# dental-unit-AS5600_v1_0.net
KiCad netlist of a schematic drawn in Altium Designer
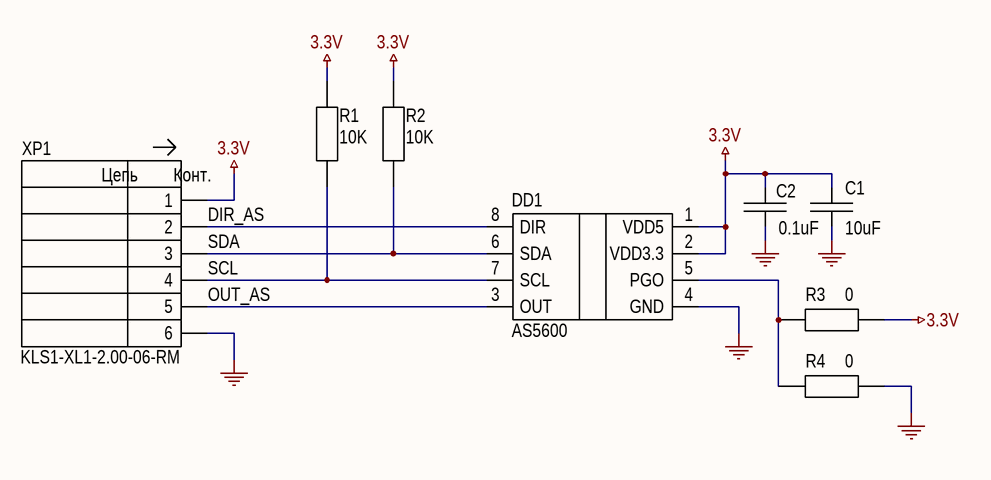
[diagram p0: dental-unit-AS5600 v1_0.SchDoc]

(export (version "E")
  (design (tool "Eeschema 10.0.6"))
  (components
    (comp (ref "C1")
      (value "10uF")
      (footprint "CC_0603")
      (description "Cap Ceramic, 0603, 10u, 10%, 16V, X5R (Sumsung)")
      (fields (field (name "Comment") "CL10A106KP8NNNC"))
      (libsource (lib "my_discrete_new") (part "C"))
    )
    (comp (ref "C2")
      (value "0.1uF")
      (footprint "CC_0603")
      (description "Cap Ceramic, 0603, 0.1u, 10%, 16V, X7R (Yageo)")
      (fields (field (name "Comment") "CC0603KRX7R5BB104"))
      (libsource (lib "my_discrete_new") (part "C"))
    )
    (comp (ref "DD1")
      (value "AS5600")
      (footprint "SOIC-8")
      (description "12-Bit Programmable Contactless\r\nPotentiometer")
      (libsource (lib "my_microschems_new") (part "AS5600"))
    )
    (comp (ref "R1")
      (value "10K")
      (footprint "RC_0603")
      (description "Res, 0603, 10K, 1%, 0.25W (ф. Yageo)")
      (fields (field (name "POWER") "0.25W") (field (name "Comment") "AC0603FR-0710KL"))
      (libsource (lib "my_discrete_new") (part "R"))
    )
    (comp (ref "R2")
      (value "10K")
      (footprint "RC_0603")
      (description "Res, 0603, 10K, 1%, 0.25W (ф. Yageo)")
      (fields (field (name "POWER") "0.25W") (field (name "Comment") "AC0603FR-0710KL"))
      (libsource (lib "my_discrete_new") (part "R"))
    )
    (comp (ref "R3")
      (value "0")
      (footprint "RC_0603")
      (description "Res, 0603, 0, 1%, 0.25W (ф. Yageo)")
      (fields (field (name "POWER") "0.25W") (field (name "Comment") "AC0603FR-070RL"))
      (libsource (lib "my_discrete_new") (part "R"))
    )
    (comp (ref "R4")
      (value "0")
      (footprint "RC_0603")
      (description "Res, 0603, 0, 1%, 0.25W (ф. Yageo)")
      (fields (field (name "POWER") "0.25W") (field (name "Comment") "AC0603FR-070RL"))
      (libsource (lib "my_discrete_new") (part "R"))
    )
    (comp (ref "XP1")
      (value "KLS1-XL1-2.00-06-RM")
      (footprint "KLS1-XL1-2.00-06-RM")
      (description "2.0mm, 6pin, KLS")
      (libsource (lib "my_connectors_new") (part "KLS1-XL1-2.00-06-x"))
    )
  )
  (nets
    (net (code "1") (name "/DIR_AS") (class "Default")
      (node (ref "DD1") (pin "8") (pinfunction "DIR_8") (pintype "passive"))
      (node (ref "XP1") (pin "2") (pinfunction "2_2") (pintype "passive"))
    )
    (net (code "2") (name "/OUT_AS") (class "Default")
      (node (ref "DD1") (pin "3") (pinfunction "OUT_3") (pintype "passive"))
      (node (ref "XP1") (pin "5") (pinfunction "5_5") (pintype "passive"))
    )
    (net (code "3") (name "/SCL") (class "Default")
      (node (ref "DD1") (pin "7") (pinfunction "SCL_7") (pintype "passive"))
      (node (ref "R1") (pin "1") (pinfunction "1_1") (pintype "passive"))
      (node (ref "XP1") (pin "4") (pinfunction "4_4") (pintype "passive"))
    )
    (net (code "4") (name "/SDA") (class "Default")
      (node (ref "DD1") (pin "6") (pinfunction "SDA_6") (pintype "passive"))
      (node (ref "R2") (pin "1") (pinfunction "1_1") (pintype "passive"))
      (node (ref "XP1") (pin "3") (pinfunction "3_3") (pintype "passive"))
    )
    (net (code "5") (name "3.3V") (class "Default")
      (node (ref "C1") (pin "2") (pinfunction "2_2") (pintype "passive"))
      (node (ref "C2") (pin "2") (pinfunction "2_2") (pintype "passive"))
      (node (ref "DD1") (pin "1") (pinfunction "VDD5_1") (pintype "passive"))
      (node (ref "DD1") (pin "2") (pinfunction "VDD3.3_2") (pintype "passive"))
      (node (ref "R1") (pin "2") (pinfunction "2_2") (pintype "passive"))
      (node (ref "R2") (pin "2") (pinfunction "2_2") (pintype "passive"))
      (node (ref "R3") (pin "2") (pinfunction "2_2") (pintype "passive"))
      (node (ref "XP1") (pin "1") (pinfunction "1_1") (pintype "passive"))
    )
    (net (code "6") (name "GND") (class "Default")
      (node (ref "C1") (pin "1") (pinfunction "1_1") (pintype "passive"))
      (node (ref "C2") (pin "1") (pinfunction "1_1") (pintype "passive"))
      (node (ref "DD1") (pin "4") (pinfunction "GND_4") (pintype "passive"))
      (node (ref "R4") (pin "2") (pinfunction "2_2") (pintype "passive"))
      (node (ref "XP1") (pin "6") (pinfunction "6_6") (pintype "passive"))
    )
    (net (code "7") (name "Net-(DD1-PGO)") (class "Default")
      (node (ref "DD1") (pin "5") (pinfunction "PGO_5") (pintype "passive"))
      (node (ref "R3") (pin "1") (pinfunction "1_1") (pintype "passive"))
      (node (ref "R4") (pin "1") (pinfunction "1_1") (pintype "passive"))
    )
  )
)
